# nand.net
KiCad netlist of a schematic drawn in EAGLE
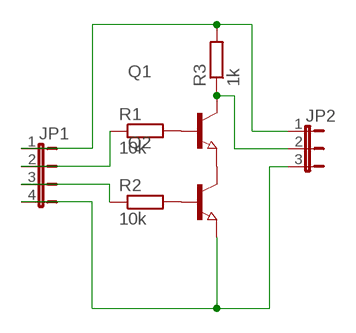
[diagram p0: schematic, sheet 1]

(export (version "E")
  (design (tool "Eeschema 10.0.6"))
  (components
    (comp (ref "JP1")
      (value "JP4E")
      (footprint "eagle-import:JP4")
      (libsource (lib "eagle-import") (part "JP4E"))
    )
    (comp (ref "JP2")
      (value "JP2W")
      (footprint "eagle-import:JP2W")
      (libsource (lib "eagle-import") (part "JP2W"))
    )
    (comp (ref "Q1")
      (value "NPN-TRANSISTOR_SOT23")
      (footprint "eagle-import:SOT23")
      (libsource (lib "eagle-import") (part "NPN-TRANSISTOR_SOT23"))
    )
    (comp (ref "Q2")
      (value "NPN-TRANSISTOR_SOT23")
      (footprint "eagle-import:SOT23")
      (libsource (lib "eagle-import") (part "NPN-TRANSISTOR_SOT23"))
    )
    (comp (ref "R1")
      (value "10k")
      (footprint "eagle-import:R1206")
      (libsource (lib "eagle-import") (part "R-EU_R1206"))
    )
    (comp (ref "R2")
      (value "10k")
      (footprint "eagle-import:R1206")
      (libsource (lib "eagle-import") (part "R-EU_R1206"))
    )
    (comp (ref "R3")
      (value "1k")
      (footprint "eagle-import:R1206")
      (libsource (lib "eagle-import") (part "R-EU_R1206"))
    )
  )
  (nets
    (net (code "1") (name "Net-(JP1-Pad1)") (class "Default")
      (node (ref "JP1") (pin "1") (pinfunction "1_1") (pintype "passive"))
      (node (ref "JP2") (pin "1") (pinfunction "1_1") (pintype "passive"))
      (node (ref "R3") (pin "2") (pinfunction "2_2") (pintype "passive"))
    )
    (net (code "2") (name "Net-(JP1-Pad2)") (class "Default")
      (node (ref "JP1") (pin "2") (pinfunction "2_2") (pintype "passive"))
      (node (ref "R1") (pin "1") (pinfunction "1_1") (pintype "passive"))
    )
    (net (code "3") (name "Net-(JP1-Pad3)") (class "Default")
      (node (ref "JP1") (pin "3") (pinfunction "3_3") (pintype "passive"))
      (node (ref "R2") (pin "1") (pinfunction "1_1") (pintype "passive"))
    )
    (net (code "4") (name "Net-(Q1-B)") (class "Default")
      (node (ref "Q1") (pin "1") (pinfunction "B_1") (pintype "passive"))
      (node (ref "R1") (pin "2") (pinfunction "2_2") (pintype "passive"))
    )
    (net (code "5") (name "Net-(Q1-C)") (class "Default")
      (node (ref "JP2") (pin "2") (pinfunction "2_2") (pintype "passive"))
      (node (ref "Q1") (pin "3") (pinfunction "C_3") (pintype "passive"))
      (node (ref "R3") (pin "1") (pinfunction "1_1") (pintype "passive"))
    )
    (net (code "6") (name "Net-(Q1-E)") (class "Default")
      (node (ref "Q1") (pin "2") (pinfunction "E_2") (pintype "passive"))
      (node (ref "Q2") (pin "3") (pinfunction "C_3") (pintype "passive"))
    )
    (net (code "7") (name "Net-(Q2-B)") (class "Default")
      (node (ref "Q2") (pin "1") (pinfunction "B_1") (pintype "passive"))
      (node (ref "R2") (pin "2") (pinfunction "2_2") (pintype "passive"))
    )
    (net (code "8") (name "Net-(Q2-E)") (class "Default")
      (node (ref "JP1") (pin "4") (pinfunction "4_4") (pintype "passive"))
      (node (ref "JP2") (pin "3") (pinfunction "3_3") (pintype "passive"))
      (node (ref "Q2") (pin "2") (pinfunction "E_2") (pintype "passive"))
    )
  )
)
